# LoRa_PWR_Monitor.net
KiCad netlist of a schematic drawn in Altium Designer
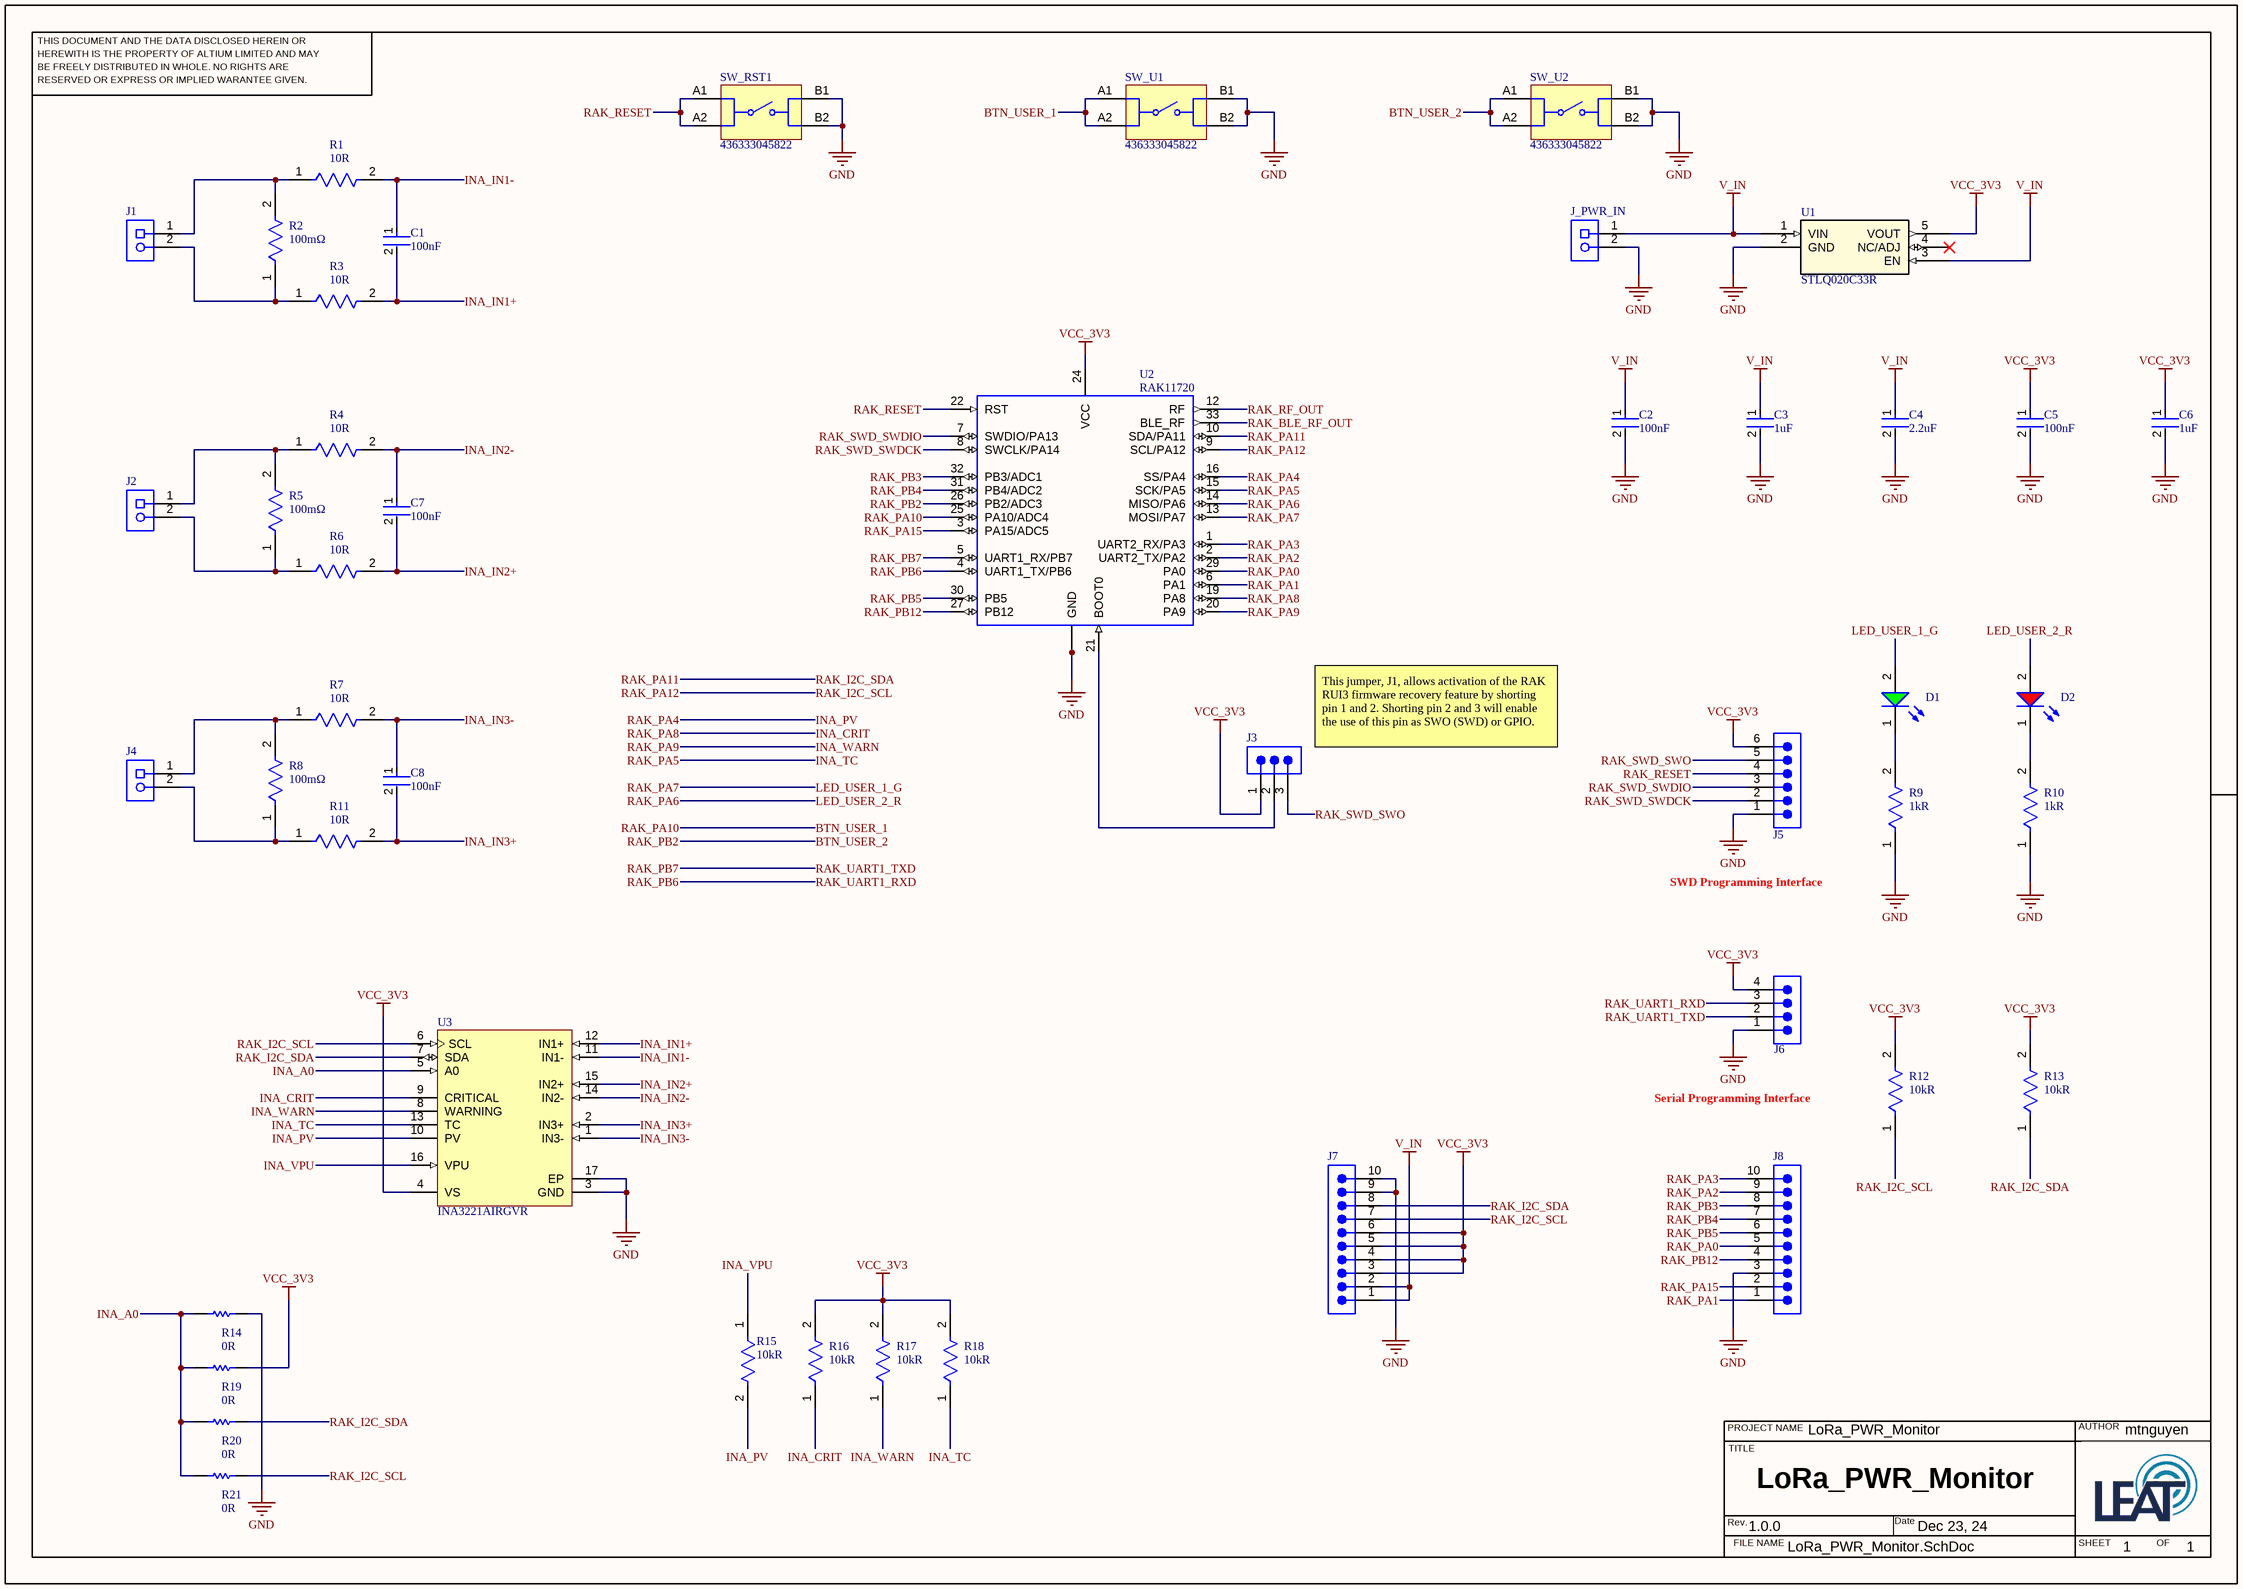
[diagram p0: LoRa_PWR_Monitor.SchDoc]

(export (version "E")
  (design (tool "Eeschema 10.0.6"))
  (components
    (comp (ref "C1")
      (value "0402ZD104KAT2A")
      (footprint "FP-0402-L_1_0_1-W_0_5_0_1-IPC_C")
      (description "General Purpose Ceramic Capacitor, 0402, 100nF, 10%, X5R, 15%, 10V")
      (fields
        (field (name "VOLTAGE") "10V")
        (field (name "TOLERANCE") "10%")
        (field (name "CAPACITANCE") "100nF")
      )
      (libsource (lib "Altium Content Vault") (part "b4654b650e69147ec39a6b967a45e02"))
    )
    (comp (ref "C2")
      (value "0402ZD104KAT2A")
      (footprint "FP-0402-L_1_0_1-W_0_5_0_1-IPC_C")
      (description "General Purpose Ceramic Capacitor, 0402, 100nF, 10%, X5R, 15%, 10V")
      (fields
        (field (name "VOLTAGE") "10V")
        (field (name "TOLERANCE") "10%")
        (field (name "CAPACITANCE") "100nF")
      )
      (libsource (lib "Altium Content Vault") (part "b4654b650e69147ec39a6b967a45e02"))
    )
    (comp (ref "C3")
      (value "EMK105BJ105KV-F")
      (footprint "FP-0402-L_1_0_0_05-W_0_5-IPC_A")
      (description "None")
      (fields (field (name "TOLERANCE") "10%") (field (name "CAPACITANCE") "1uF"))
      (libsource (lib "Altium Content Vault") (part "b4654b650e69147ec39a6b967a45e02"))
    )
    (comp (ref "C4")
      (value "C1005X5R1A225K050BC")
      (footprint "FP-C1005-050-0_05-IPC_A")
      (description "Multilayer Ceramic Capacitors 2.2μF ±10% 10V X5R SMD 0402")
      (fields
        (field (name "TOLERANCE") "10%")
        (field (name "VOLTAGE") "10V")
        (field (name "CAPACITANCE") "2.2uF")
      )
      (libsource (lib "Altium Content Vault") (part "b4654b650e69147ec39a6b967a45e02"))
    )
    (comp (ref "C5")
      (value "0402ZD104KAT2A")
      (footprint "FP-0402-L_1_0_1-W_0_5_0_1-IPC_C")
      (description "General Purpose Ceramic Capacitor, 0402, 100nF, 10%, X5R, 15%, 10V")
      (fields
        (field (name "VOLTAGE") "10V")
        (field (name "TOLERANCE") "10%")
        (field (name "CAPACITANCE") "100nF")
      )
      (libsource (lib "Altium Content Vault") (part "b4654b650e69147ec39a6b967a45e02"))
    )
    (comp (ref "C6")
      (value "EMK105BJ105KV-F")
      (footprint "FP-0402-L_1_0_0_05-W_0_5-IPC_A")
      (description "None")
      (fields (field (name "TOLERANCE") "10%") (field (name "CAPACITANCE") "1uF"))
      (libsource (lib "Altium Content Vault") (part "b4654b650e69147ec39a6b967a45e02"))
    )
    (comp (ref "C7")
      (value "0402ZD104KAT2A")
      (footprint "FP-0402-L_1_0_1-W_0_5_0_1-IPC_C")
      (description "General Purpose Ceramic Capacitor, 0402, 100nF, 10%, X5R, 15%, 10V")
      (fields
        (field (name "VOLTAGE") "10V")
        (field (name "TOLERANCE") "10%")
        (field (name "CAPACITANCE") "100nF")
      )
      (libsource (lib "Altium Content Vault") (part "b4654b650e69147ec39a6b967a45e02"))
    )
    (comp (ref "C8")
      (value "0402ZD104KAT2A")
      (footprint "FP-0402-L_1_0_1-W_0_5_0_1-IPC_C")
      (description "General Purpose Ceramic Capacitor, 0402, 100nF, 10%, X5R, 15%, 10V")
      (fields
        (field (name "VOLTAGE") "10V")
        (field (name "TOLERANCE") "10%")
        (field (name "CAPACITANCE") "100nF")
      )
      (libsource (lib "Altium Content Vault") (part "b4654b650e69147ec39a6b967a45e02"))
    )
    (comp (ref "D1")
      (value "150060VS75000")
      (footprint "WL-SMCW_0603_150060xx75000")
      (description "WURTH ELEKTRONIK - 150060VS75000 - LED, Green, SMD, 0603, 30 mA, 2 V, 570 nm")
      (libsource (lib "Altium Content Vault") (part "LED_Green_2A-1K"))
    )
    (comp (ref "D2")
      (value "150060RS75000")
      (footprint "WL-SMCW_0603_150060xx75000")
      (description "LED Low-Power Uni-Color Red 630nm 2V 2-Pin Chip 0603(1608Metric) T/R")
      (libsource (lib "Altium Content Vault") (part "LED_Red_2A-1K"))
    )
    (comp (ref "J1")
      (value "1729128")
      (footprint "PHOE-1729128-2_V")
      (description "PCB Terminal Block, 13.5 A, 400 V, 2-Pin THD, RoHS, Bulk")
      (fields (field (name "MANUFACTURER") "Phoenix Contact"))
      (libsource (lib "Altium Content Vault") (part "CN-2P-F-R2"))
    )
    (comp (ref "J2")
      (value "1729128")
      (footprint "PHOE-1729128-2_V")
      (description "PCB Terminal Block, 13.5 A, 400 V, 2-Pin THD, RoHS, Bulk")
      (fields (field (name "MANUFACTURER") "Phoenix Contact"))
      (libsource (lib "Altium Content Vault") (part "CN-2P-F-R2"))
    )
    (comp (ref "J3")
      (value "61300311121")
      (footprint "61300311121")
      (libsource (lib "Altium Content Vault") (part "Header_Male_1R_03P"))
    )
    (comp (ref "J4")
      (value "1729128")
      (footprint "PHOE-1729128-2_V")
      (description "PCB Terminal Block, 13.5 A, 400 V, 2-Pin THD, RoHS, Bulk")
      (fields (field (name "MANUFACTURER") "Phoenix Contact"))
      (libsource (lib "Altium Content Vault") (part "CN-2P-F-R2"))
    )
    (comp (ref "J5")
      (value "61300611121")
      (footprint "61300611121")
      (libsource (lib "Altium Content Vault") (part "Header_Male_1R_06P"))
    )
    (comp (ref "J6")
      (value "61300411121")
      (footprint "61300411121")
      (libsource (lib "Altium Content Vault") (part "Header_Male_1R_04P"))
    )
    (comp (ref "J7")
      (value "61301011121")
      (footprint "61301011121")
      (libsource (lib "Altium Content Vault") (part "Header_Male_1R_10P"))
    )
    (comp (ref "J8")
      (value "61301011121")
      (footprint "61301011121")
      (libsource (lib "Altium Content Vault") (part "Header_Male_1R_10P"))
    )
    (comp (ref "J_PWR_IN")
      (value "1729128")
      (footprint "PHOE-1729128-2_V")
      (description "PCB Terminal Block, 13.5 A, 400 V, 2-Pin THD, RoHS, Bulk")
      (fields (field (name "MANUFACTURER") "Phoenix Contact"))
      (libsource (lib "Altium Content Vault") (part "CN-2P-F-R2"))
    )
    (comp (ref "R1")
      (value "MCR01MZPF10R0")
      (footprint "FP-MCR01-IPC_C")
      (description "Thick Film Chip Resistor, 0402, 10Ω, 1%, 100ppm/°C, 0.063W, 50V")
      (fields (field (name "RESISTANCE") "10R") (field (name "TOLERANCE") "1%"))
      (libsource (lib "Altium Content Vault") (part "1029c3af85768c4190bb7ad29bc67b5"))
    )
    (comp (ref "R2")
      (value "100mΩ")
      (footprint "FP-CRM2512-MFG")
      (description "RES 0.1 OHM 1% 2W 2512")
      (fields (field (name "MANUFACTURER") "Bourns") (field (name "VOLTAGE") "1.349V"))
      (libsource (lib "Altium Content Vault") (part "1029c3af85768c4190bb7ad29bc67b5"))
    )
    (comp (ref "R3")
      (value "MCR01MZPF10R0")
      (footprint "FP-MCR01-IPC_C")
      (description "Thick Film Chip Resistor, 0402, 10Ω, 1%, 100ppm/°C, 0.063W, 50V")
      (fields (field (name "RESISTANCE") "10R") (field (name "TOLERANCE") "1%"))
      (libsource (lib "Altium Content Vault") (part "1029c3af85768c4190bb7ad29bc67b5"))
    )
    (comp (ref "R4")
      (value "MCR01MZPF10R0")
      (footprint "FP-MCR01-IPC_C")
      (description "Thick Film Chip Resistor, 0402, 10Ω, 1%, 100ppm/°C, 0.063W, 50V")
      (fields (field (name "RESISTANCE") "10R") (field (name "TOLERANCE") "1%"))
      (libsource (lib "Altium Content Vault") (part "1029c3af85768c4190bb7ad29bc67b5"))
    )
    (comp (ref "R5")
      (value "100mΩ")
      (footprint "FP-CRM2512-MFG")
      (description "RES 0.1 OHM 1% 2W 2512")
      (fields (field (name "MANUFACTURER") "Bourns") (field (name "VOLTAGE") "1.349V"))
      (libsource (lib "Altium Content Vault") (part "1029c3af85768c4190bb7ad29bc67b5"))
    )
    (comp (ref "R6")
      (value "MCR01MZPF10R0")
      (footprint "FP-MCR01-IPC_C")
      (description "Thick Film Chip Resistor, 0402, 10Ω, 1%, 100ppm/°C, 0.063W, 50V")
      (fields (field (name "RESISTANCE") "10R") (field (name "TOLERANCE") "1%"))
      (libsource (lib "Altium Content Vault") (part "1029c3af85768c4190bb7ad29bc67b5"))
    )
    (comp (ref "R7")
      (value "MCR01MZPF10R0")
      (footprint "FP-MCR01-IPC_C")
      (description "Thick Film Chip Resistor, 0402, 10Ω, 1%, 100ppm/°C, 0.063W, 50V")
      (fields (field (name "RESISTANCE") "10R") (field (name "TOLERANCE") "1%"))
      (libsource (lib "Altium Content Vault") (part "1029c3af85768c4190bb7ad29bc67b5"))
    )
    (comp (ref "R8")
      (value "100mΩ")
      (footprint "FP-CRM2512-MFG")
      (description "RES 0.1 OHM 1% 2W 2512")
      (fields (field (name "MANUFACTURER") "Bourns") (field (name "VOLTAGE") "1.349V"))
      (libsource (lib "Altium Content Vault") (part "1029c3af85768c4190bb7ad29bc67b5"))
    )
    (comp (ref "R9")
      (value "RMCF0402FT1K00")
      (footprint "FP-RMCF0402-IPC_A")
      (description "1kΩ ±1% 0.063W 0402 Thick Film Chip Resistor AEC-Q200 compliant")
      (fields (field (name "TOLERANCE") "1%") (field (name "RESISTANCE") "1kR"))
      (libsource (lib "Altium Content Vault") (part "1029c3af85768c4190bb7ad29bc67b5"))
    )
    (comp (ref "R10")
      (value "RMCF0402FT1K00")
      (footprint "FP-RMCF0402-IPC_A")
      (description "1kΩ ±1% 0.063W 0402 Thick Film Chip Resistor AEC-Q200 compliant")
      (fields (field (name "TOLERANCE") "1%") (field (name "RESISTANCE") "1kR"))
      (libsource (lib "Altium Content Vault") (part "1029c3af85768c4190bb7ad29bc67b5"))
    )
    (comp (ref "R11")
      (value "MCR01MZPF10R0")
      (footprint "FP-MCR01-IPC_C")
      (description "Thick Film Chip Resistor, 0402, 10Ω, 1%, 100ppm/°C, 0.063W, 50V")
      (fields (field (name "RESISTANCE") "10R") (field (name "TOLERANCE") "1%"))
      (libsource (lib "Altium Content Vault") (part "1029c3af85768c4190bb7ad29bc67b5"))
    )
    (comp (ref "R12")
      (value "RMCF0402FT10K0")
      (footprint "FP-RMCF0402-IPC_C")
      (description "10kΩ ±1% 0.063W 0402 Thick Film Chip Resistor AEC-Q200 compliant")
      (fields (field (name "RESISTANCE") "10kR") (field (name "TOLERANCE") "1%"))
      (libsource (lib "Altium Content Vault") (part "1029c3af85768c4190bb7ad29bc67b5"))
    )
    (comp (ref "R13")
      (value "RMCF0402FT10K0")
      (footprint "FP-RMCF0402-IPC_C")
      (description "10kΩ ±1% 0.063W 0402 Thick Film Chip Resistor AEC-Q200 compliant")
      (fields (field (name "RESISTANCE") "10kR") (field (name "TOLERANCE") "1%"))
      (libsource (lib "Altium Content Vault") (part "1029c3af85768c4190bb7ad29bc67b5"))
    )
    (comp (ref "R14")
      (value "RC1005J000CS")
      (footprint "RESC1005X40X25LL05T10")
      (description "Chip Resistor, 0 Ohm, +/- 5%, -55 to 125 degC, 0402 (1005 Metric), RoHS, Tape and Reel")
      (fields (field (name "RESISTANCE") "0R") (field (name "MANUFACTURER") "Samsung Electro-Mechanics"))
      (libsource (lib "Altium Content Vault") (part "RES-2"))
    )
    (comp (ref "R15")
      (value "RMCF0402FT10K0")
      (footprint "FP-RMCF0402-IPC_C")
      (description "10kΩ ±1% 0.063W 0402 Thick Film Chip Resistor AEC-Q200 compliant")
      (fields (field (name "RESISTANCE") "10kR") (field (name "TOLERANCE") "1%"))
      (libsource (lib "Altium Content Vault") (part "1029c3af85768c4190bb7ad29bc67b5"))
    )
    (comp (ref "R16")
      (value "RMCF0402FT10K0")
      (footprint "FP-RMCF0402-IPC_C")
      (description "10kΩ ±1% 0.063W 0402 Thick Film Chip Resistor AEC-Q200 compliant")
      (fields (field (name "RESISTANCE") "10kR") (field (name "TOLERANCE") "1%"))
      (libsource (lib "Altium Content Vault") (part "1029c3af85768c4190bb7ad29bc67b5"))
    )
    (comp (ref "R17")
      (value "RMCF0402FT10K0")
      (footprint "FP-RMCF0402-IPC_C")
      (description "10kΩ ±1% 0.063W 0402 Thick Film Chip Resistor AEC-Q200 compliant")
      (fields (field (name "RESISTANCE") "10kR") (field (name "TOLERANCE") "1%"))
      (libsource (lib "Altium Content Vault") (part "1029c3af85768c4190bb7ad29bc67b5"))
    )
    (comp (ref "R18")
      (value "RMCF0402FT10K0")
      (footprint "FP-RMCF0402-IPC_C")
      (description "10kΩ ±1% 0.063W 0402 Thick Film Chip Resistor AEC-Q200 compliant")
      (fields (field (name "RESISTANCE") "10kR") (field (name "TOLERANCE") "1%"))
      (libsource (lib "Altium Content Vault") (part "1029c3af85768c4190bb7ad29bc67b5"))
    )
    (comp (ref "R19")
      (value "RC1005J000CS")
      (footprint "RESC1005X40X25LL05T10")
      (description "Chip Resistor, 0 Ohm, +/- 5%, -55 to 125 degC, 0402 (1005 Metric), RoHS, Tape and Reel")
      (fields (field (name "RESISTANCE") "0R") (field (name "MANUFACTURER") "Samsung Electro-Mechanics"))
      (libsource (lib "Altium Content Vault") (part "RES-2"))
    )
    (comp (ref "R20")
      (value "RC1005J000CS")
      (footprint "RESC1005X40X25LL05T10")
      (description "Chip Resistor, 0 Ohm, +/- 5%, -55 to 125 degC, 0402 (1005 Metric), RoHS, Tape and Reel")
      (fields (field (name "RESISTANCE") "0R") (field (name "MANUFACTURER") "Samsung Electro-Mechanics"))
      (libsource (lib "Altium Content Vault") (part "RES-2"))
    )
    (comp (ref "R21")
      (value "RC1005J000CS")
      (footprint "RESC1005X40X25LL05T10")
      (description "Chip Resistor, 0 Ohm, +/- 5%, -55 to 125 degC, 0402 (1005 Metric), RoHS, Tape and Reel")
      (fields (field (name "RESISTANCE") "0R") (field (name "MANUFACTURER") "Samsung Electro-Mechanics"))
      (libsource (lib "Altium Content Vault") (part "RES-2"))
    )
    (comp (ref "SW_RST1")
      (value "436333045822")
      (footprint "436333045822")
      (libsource (lib "Altium Content Vault") (part "SPST-NO_4P"))
    )
    (comp (ref "SW_U1")
      (value "436333045822")
      (footprint "436333045822")
      (libsource (lib "Altium Content Vault") (part "SPST-NO_4P"))
    )
    (comp (ref "SW_U2")
      (value "436333045822")
      (footprint "436333045822")
      (libsource (lib "Altium Content Vault") (part "SPST-NO_4P"))
    )
    (comp (ref "U1")
      (value "STLQ020C33R")
      (footprint "SOT323-5L_STM")
      (description "No Description Available")
      (fields (field (name "COPYRIGHT") "Copyright (C) 2023 Ultra Librarian. All rights reserved."))
      (libsource (lib "EchoStar") (part "STLQ020C33R"))
    )
    (comp (ref "U2")
      (value "RAK11720")
      (footprint "RAK11720")
      (description "RAK11720 Ambiq Apollo3 Blue SX1262 LoRa Bluetooth Module for LoRaWAN")
      (fields (field (name "MP") "RAK3172") (field (name "MF") "Shenzhen RAKwireless Technology Co.,Ltd."))
      (libsource (lib "RAK3172") (part "RAK11720"))
    )
    (comp (ref "U3")
      (value "INA3221AIRGVR")
      (footprint "RGV0016A_V")
      (fields (field (name "MANUFACTURER") "Texas Instruments"))
      (libsource (lib "Altium Content Vault") (part "TI-INA3221-RGV-16"))
    )
  )
  (nets
    (net (code "1") (name "/BTN_USER_1") (class "Default")
      (node (ref "SW_U1") (pin "A1") (pinfunction "A1_A1") (pintype "passive"))
      (node (ref "SW_U1") (pin "A2") (pinfunction "A2_A2") (pintype "passive"))
      (node (ref "U2") (pin "25") (pinfunction "PA10/ADC4_25") (pintype "bidirectional"))
    )
    (net (code "2") (name "/BTN_USER_2") (class "Default")
      (node (ref "SW_U2") (pin "A1") (pinfunction "A1_A1") (pintype "passive"))
      (node (ref "SW_U2") (pin "A2") (pinfunction "A2_A2") (pintype "passive"))
      (node (ref "U2") (pin "26") (pinfunction "PB2/ADC3_26") (pintype "bidirectional"))
    )
    (net (code "3") (name "/INA_A0") (class "Default")
      (node (ref "R14") (pin "1") (pinfunction "1_1") (pintype "passive"))
      (node (ref "R19") (pin "1") (pinfunction "1_1") (pintype "passive"))
      (node (ref "R20") (pin "1") (pinfunction "1_1") (pintype "passive"))
      (node (ref "R21") (pin "1") (pinfunction "1_1") (pintype "passive"))
      (node (ref "U3") (pin "5") (pinfunction "A0_5") (pintype "input"))
    )
    (net (code "4") (name "/INA_CRIT") (class "Default")
      (node (ref "R16") (pin "1") (pinfunction "1_1") (pintype "passive"))
      (node (ref "U2") (pin "19") (pinfunction "PA8_19") (pintype "bidirectional"))
      (node (ref "U3") (pin "9") (pinfunction "CRITICAL_9") (pintype "open_collector"))
    )
    (net (code "5") (name "/INA_IN1+") (class "Default")
      (node (ref "C1") (pin "2") (pinfunction "2_2") (pintype "passive"))
      (node (ref "R3") (pin "2") (pinfunction "2_2") (pintype "passive"))
      (node (ref "U3") (pin "12") (pinfunction "IN1+_12") (pintype "input"))
    )
    (net (code "6") (name "/INA_IN1-") (class "Default")
      (node (ref "C1") (pin "1") (pinfunction "1_1") (pintype "passive"))
      (node (ref "R1") (pin "2") (pinfunction "2_2") (pintype "passive"))
      (node (ref "U3") (pin "11") (pinfunction "IN1-_11") (pintype "input"))
    )
    (net (code "7") (name "/INA_IN2+") (class "Default")
      (node (ref "C7") (pin "2") (pinfunction "2_2") (pintype "passive"))
      (node (ref "R6") (pin "2") (pinfunction "2_2") (pintype "passive"))
      (node (ref "U3") (pin "15") (pinfunction "IN2+_15") (pintype "input"))
    )
    (net (code "8") (name "/INA_IN2-") (class "Default")
      (node (ref "C7") (pin "1") (pinfunction "1_1") (pintype "passive"))
      (node (ref "R4") (pin "2") (pinfunction "2_2") (pintype "passive"))
      (node (ref "U3") (pin "14") (pinfunction "IN2-_14") (pintype "input"))
    )
    (net (code "9") (name "/INA_IN3+") (class "Default")
      (node (ref "C8") (pin "2") (pinfunction "2_2") (pintype "passive"))
      (node (ref "R11") (pin "2") (pinfunction "2_2") (pintype "passive"))
      (node (ref "U3") (pin "2") (pinfunction "IN3+_2") (pintype "input"))
    )
    (net (code "10") (name "/INA_IN3-") (class "Default")
      (node (ref "C8") (pin "1") (pinfunction "1_1") (pintype "passive"))
      (node (ref "R7") (pin "2") (pinfunction "2_2") (pintype "passive"))
      (node (ref "U3") (pin "1") (pinfunction "IN3-_1") (pintype "input"))
    )
    (net (code "11") (name "/INA_PV") (class "Default")
      (node (ref "R15") (pin "2") (pinfunction "2_2") (pintype "passive"))
      (node (ref "U2") (pin "16") (pinfunction "SS/PA4_16") (pintype "bidirectional"))
      (node (ref "U3") (pin "10") (pinfunction "PV_10") (pintype "open_collector"))
    )
    (net (code "12") (name "/INA_TC") (class "Default")
      (node (ref "R18") (pin "1") (pinfunction "1_1") (pintype "passive"))
      (node (ref "U2") (pin "15") (pinfunction "SCK/PA5_15") (pintype "bidirectional"))
      (node (ref "U3") (pin "13") (pinfunction "TC_13") (pintype "open_collector"))
    )
    (net (code "13") (name "/INA_VPU") (class "Default")
      (node (ref "R15") (pin "1") (pinfunction "1_1") (pintype "passive"))
      (node (ref "U3") (pin "16") (pinfunction "VPU_16") (pintype "input"))
    )
    (net (code "14") (name "/INA_WARN") (class "Default")
      (node (ref "R17") (pin "1") (pinfunction "1_1") (pintype "passive"))
      (node (ref "U2") (pin "20") (pinfunction "PA9_20") (pintype "bidirectional"))
      (node (ref "U3") (pin "8") (pinfunction "WARNING_8") (pintype "open_collector"))
    )
    (net (code "15") (name "/LED_USER_1_G") (class "Default")
      (node (ref "D1") (pin "2") (pinfunction "A_2") (pintype "passive"))
      (node (ref "U2") (pin "13") (pinfunction "MOSI/PA7_13") (pintype "bidirectional"))
    )
    (net (code "16") (name "/LED_USER_2_R") (class "Default")
      (node (ref "D2") (pin "2") (pinfunction "A_2") (pintype "passive"))
      (node (ref "U2") (pin "14") (pinfunction "MISO/PA6_14") (pintype "bidirectional"))
    )
    (net (code "17") (name "/RAK_BLE_RF_OUT") (class "Default")
      (node (ref "U2") (pin "33") (pinfunction "BLE_RF_33") (pintype "output"))
    )
    (net (code "18") (name "/RAK_I2C_SCL") (class "Default")
      (node (ref "J7") (pin "7") (pinfunction "7_7") (pintype "passive"))
      (node (ref "R12") (pin "1") (pinfunction "1_1") (pintype "passive"))
      (node (ref "R21") (pin "2") (pinfunction "2_2") (pintype "passive"))
      (node (ref "U2") (pin "9") (pinfunction "SCL/PA12_9") (pintype "bidirectional"))
      (node (ref "U3") (pin "6") (pinfunction "SCL_6") (pintype "input"))
    )
    (net (code "19") (name "/RAK_I2C_SDA") (class "Default")
      (node (ref "J7") (pin "8") (pinfunction "8_8") (pintype "passive"))
      (node (ref "R13") (pin "1") (pinfunction "1_1") (pintype "passive"))
      (node (ref "R20") (pin "2") (pinfunction "2_2") (pintype "passive"))
      (node (ref "U2") (pin "10") (pinfunction "SDA/PA11_10") (pintype "bidirectional"))
      (node (ref "U3") (pin "7") (pinfunction "SDA_7") (pintype "bidirectional"))
    )
    (net (code "20") (name "/RAK_PA0") (class "Default")
      (node (ref "J8") (pin "5") (pinfunction "5_5") (pintype "passive"))
      (node (ref "U2") (pin "29") (pinfunction "PA0_29") (pintype "bidirectional"))
    )
    (net (code "21") (name "/RAK_PA1") (class "Default")
      (node (ref "J8") (pin "1") (pinfunction "1_1") (pintype "passive"))
      (node (ref "U2") (pin "6") (pinfunction "PA1_6") (pintype "bidirectional"))
    )
    (net (code "22") (name "/RAK_PA2") (class "Default")
      (node (ref "J8") (pin "9") (pinfunction "9_9") (pintype "passive"))
      (node (ref "U2") (pin "2") (pinfunction "UART2_TX/PA2_2") (pintype "bidirectional"))
    )
    (net (code "23") (name "/RAK_PA3") (class "Default")
      (node (ref "J8") (pin "10") (pinfunction "10_10") (pintype "passive"))
      (node (ref "U2") (pin "1") (pinfunction "UART2_RX/PA3_1") (pintype "bidirectional"))
    )
    (net (code "24") (name "/RAK_PA15") (class "Default")
      (node (ref "J8") (pin "2") (pinfunction "2_2") (pintype "passive"))
      (node (ref "U2") (pin "3") (pinfunction "PA15/ADC5_3") (pintype "bidirectional"))
    )
    (net (code "25") (name "/RAK_PB3") (class "Default")
      (node (ref "J8") (pin "8") (pinfunction "8_8") (pintype "passive"))
      (node (ref "U2") (pin "32") (pinfunction "PB3/ADC1_32") (pintype "bidirectional"))
    )
    (net (code "26") (name "/RAK_PB4") (class "Default")
      (node (ref "J8") (pin "7") (pinfunction "7_7") (pintype "passive"))
      (node (ref "U2") (pin "31") (pinfunction "PB4/ADC2_31") (pintype "bidirectional"))
    )
    (net (code "27") (name "/RAK_PB5") (class "Default")
      (node (ref "J8") (pin "6") (pinfunction "6_6") (pintype "passive"))
      (node (ref "U2") (pin "30") (pinfunction "PB5_30") (pintype "bidirectional"))
    )
    (net (code "28") (name "/RAK_PB6") (class "Default")
      (node (ref "J6") (pin "3") (pinfunction "3_3") (pintype "passive"))
      (node (ref "U2") (pin "4") (pinfunction "UART1_TX/PB6_4") (pintype "bidirectional"))
    )
    (net (code "29") (name "/RAK_PB7") (class "Default")
      (node (ref "J6") (pin "2") (pinfunction "2_2") (pintype "passive"))
      (node (ref "U2") (pin "5") (pinfunction "UART1_RX/PB7_5") (pintype "bidirectional"))
    )
    (net (code "30") (name "/RAK_PB12") (class "Default")
      (node (ref "J8") (pin "4") (pinfunction "4_4") (pintype "passive"))
      (node (ref "U2") (pin "27") (pinfunction "PB12_27") (pintype "bidirectional"))
    )
    (net (code "31") (name "/RAK_RESET") (class "Default")
      (node (ref "J5") (pin "4") (pinfunction "4_4") (pintype "passive"))
      (node (ref "SW_RST1") (pin "A1") (pinfunction "A1_A1") (pintype "passive"))
      (node (ref "SW_RST1") (pin "A2") (pinfunction "A2_A2") (pintype "passive"))
      (node (ref "U2") (pin "22") (pinfunction "RST_22") (pintype "input"))
    )
    (net (code "32") (name "/RAK_RF_OUT") (class "Default")
      (node (ref "U2") (pin "12") (pinfunction "RF_12") (pintype "output"))
    )
    (net (code "33") (name "/RAK_SWD_SWDCK") (class "Default")
      (node (ref "J5") (pin "2") (pinfunction "2_2") (pintype "passive"))
      (node (ref "U2") (pin "8") (pinfunction "SWCLK/PA14_8") (pintype "bidirectional"))
    )
    (net (code "34") (name "/RAK_SWD_SWDIO") (class "Default")
      (node (ref "J5") (pin "3") (pinfunction "3_3") (pintype "passive"))
      (node (ref "U2") (pin "7") (pinfunction "SWDIO/PA13_7") (pintype "bidirectional"))
    )
    (net (code "35") (name "/RAK_SWD_SWO") (class "Default")
      (node (ref "J3") (pin "3") (pinfunction "3_3") (pintype "passive"))
      (node (ref "J5") (pin "5") (pinfunction "5_5") (pintype "passive"))
    )
    (net (code "36") (name "GND") (class "Default")
      (node (ref "C2") (pin "2") (pinfunction "2_2") (pintype "passive"))
      (node (ref "C3") (pin "2") (pinfunction "2_2") (pintype "passive"))
      (node (ref "C4") (pin "2") (pinfunction "2_2") (pintype "passive"))
      (node (ref "C5") (pin "2") (pinfunction "2_2") (pintype "passive"))
      (node (ref "C6") (pin "2") (pinfunction "2_2") (pintype "passive"))
      (node (ref "J5") (pin "1") (pinfunction "1_1") (pintype "passive"))
      (node (ref "J6") (pin "1") (pinfunction "1_1") (pintype "passive"))
      (node (ref "J7") (pin "10") (pinfunction "10_10") (pintype "passive"))
      (node (ref "J7") (pin "9") (pinfunction "9_9") (pintype "passive"))
      (node (ref "J8") (pin "3") (pinfunction "3_3") (pintype "passive"))
      (node (ref "J_PWR_IN") (pin "2") (pinfunction "2_2") (pintype "passive"))
      (node (ref "R10") (pin "1") (pinfunction "1_1") (pintype "passive"))
      (node (ref "R14") (pin "2") (pinfunction "2_2") (pintype "passive"))
      (node (ref "R9") (pin "1") (pinfunction "1_1") (pintype "passive"))
      (node (ref "SW_RST1") (pin "B1") (pinfunction "B1_B1") (pintype "passive"))
      (node (ref "SW_RST1") (pin "B2") (pinfunction "B2_B2") (pintype "passive"))
      (node (ref "SW_U1") (pin "B1") (pinfunction "B1_B1") (pintype "passive"))
      (node (ref "SW_U1") (pin "B2") (pinfunction "B2_B2") (pintype "passive"))
      (node (ref "SW_U2") (pin "B1") (pinfunction "B1_B1") (pintype "passive"))
      (node (ref "SW_U2") (pin "B2") (pinfunction "B2_B2") (pintype "passive"))
      (node (ref "U1") (pin "2") (pinfunction "GND_2") (pintype "power_in"))
      (node (ref "U2") (pin "11") (pinfunction "GND_11") (pintype "power_in"))
      (node (ref "U2") (pin "17") (pinfunction "GND_17") (pintype "power_in"))
      (node (ref "U2") (pin "18") (pinfunction "GND_18") (pintype "power_in"))
      (node (ref "U2") (pin "23") (pinfunction "GND_23") (pintype "power_in"))
      (node (ref "U2") (pin "28") (pinfunction "GND_28") (pintype "power_in"))
      (node (ref "U2") (pin "34") (pinfunction "GND_34") (pintype "power_in"))
      (node (ref "U3") (pin "17") (pinfunction "EP_17") (pintype "passive"))
      (node (ref "U3") (pin "3") (pinfunction "GND_3") (pintype "power_in"))
    )
    (net (code "37") (name "Net-(D1-K)") (class "Default")
      (node (ref "D1") (pin "1") (pinfunction "K_1") (pintype "passive"))
      (node (ref "R9") (pin "2") (pinfunction "2_2") (pintype "passive"))
    )
    (net (code "38") (name "Net-(D2-K)") (class "Default")
      (node (ref "D2") (pin "1") (pinfunction "K_1") (pintype "passive"))
      (node (ref "R10") (pin "2") (pinfunction "2_2") (pintype "passive"))
    )
    (net (code "39") (name "Net-(J1-Pad1)") (class "Default")
      (node (ref "J1") (pin "1") (pinfunction "1_1") (pintype "passive"))
      (node (ref "R1") (pin "1") (pinfunction "1_1") (pintype "passive"))
      (node (ref "R2") (pin "2") (pinfunction "2_2") (pintype "passive"))
    )
    (net (code "40") (name "Net-(J1-Pad2)") (class "Default")
      (node (ref "J1") (pin "2") (pinfunction "2_2") (pintype "passive"))
      (node (ref "R2") (pin "1") (pinfunction "1_1") (pintype "passive"))
      (node (ref "R3") (pin "1") (pinfunction "1_1") (pintype "passive"))
    )
    (net (code "41") (name "Net-(J2-Pad1)") (class "Default")
      (node (ref "J2") (pin "1") (pinfunction "1_1") (pintype "passive"))
      (node (ref "R4") (pin "1") (pinfunction "1_1") (pintype "passive"))
      (node (ref "R5") (pin "2") (pinfunction "2_2") (pintype "passive"))
    )
    (net (code "42") (name "Net-(J2-Pad2)") (class "Default")
      (node (ref "J2") (pin "2") (pinfunction "2_2") (pintype "passive"))
      (node (ref "R5") (pin "1") (pinfunction "1_1") (pintype "passive"))
      (node (ref "R6") (pin "1") (pinfunction "1_1") (pintype "passive"))
    )
    (net (code "43") (name "Net-(J4-Pad1)") (class "Default")
      (node (ref "J4") (pin "1") (pinfunction "1_1") (pintype "passive"))
      (node (ref "R7") (pin "1") (pinfunction "1_1") (pintype "passive"))
      (node (ref "R8") (pin "2") (pinfunction "2_2") (pintype "passive"))
    )
    (net (code "44") (name "Net-(J4-Pad2)") (class "Default")
      (node (ref "J4") (pin "2") (pinfunction "2_2") (pintype "passive"))
      (node (ref "R11") (pin "1") (pinfunction "1_1") (pintype "passive"))
      (node (ref "R8") (pin "1") (pinfunction "1_1") (pintype "passive"))
    )
    (net (code "45") (name "Net-(U2-BOOT0)") (class "Default")
      (node (ref "J3") (pin "2") (pinfunction "2_2") (pintype "passive"))
      (node (ref "U2") (pin "21") (pinfunction "BOOT0_21") (pintype "input"))
    )
    (net (code "46") (name "VCC_3V3") (class "Default")
      (node (ref "C5") (pin "1") (pinfunction "1_1") (pintype "passive"))
      (node (ref "C6") (pin "1") (pinfunction "1_1") (pintype "passive"))
      (node (ref "J3") (pin "1") (pinfunction "1_1") (pintype "passive"))
      (node (ref "J5") (pin "6") (pinfunction "6_6") (pintype "passive"))
      (node (ref "J6") (pin "4") (pinfunction "4_4") (pintype "passive"))
      (node (ref "J7") (pin "3") (pinfunction "3_3") (pintype "passive"))
      (node (ref "J7") (pin "4") (pinfunction "4_4") (pintype "passive"))
      (node (ref "J7") (pin "5") (pinfunction "5_5") (pintype "passive"))
      (node (ref "J7") (pin "6") (pinfunction "6_6") (pintype "passive"))
      (node (ref "R12") (pin "2") (pinfunction "2_2") (pintype "passive"))
      (node (ref "R13") (pin "2") (pinfunction "2_2") (pintype "passive"))
      (node (ref "R16") (pin "2") (pinfunction "2_2") (pintype "passive"))
      (node (ref "R17") (pin "2") (pinfunction "2_2") (pintype "passive"))
      (node (ref "R18") (pin "2") (pinfunction "2_2") (pintype "passive"))
      (node (ref "R19") (pin "2") (pinfunction "2_2") (pintype "passive"))
      (node (ref "U1") (pin "5") (pinfunction "VOUT_5") (pintype "output"))
      (node (ref "U2") (pin "24") (pinfunction "VCC_24") (pintype "power_in"))
      (node (ref "U3") (pin "4") (pinfunction "VS_4") (pintype "power_in"))
    )
    (net (code "47") (name "V_IN") (class "Default")
      (node (ref "C2") (pin "1") (pinfunction "1_1") (pintype "passive"))
      (node (ref "C3") (pin "1") (pinfunction "1_1") (pintype "passive"))
      (node (ref "C4") (pin "1") (pinfunction "1_1") (pintype "passive"))
      (node (ref "J7") (pin "1") (pinfunction "1_1") (pintype "passive"))
      (node (ref "J7") (pin "2") (pinfunction "2_2") (pintype "passive"))
      (node (ref "J_PWR_IN") (pin "1") (pinfunction "1_1") (pintype "passive"))
      (node (ref "U1") (pin "1") (pinfunction "VIN_1") (pintype "input"))
      (node (ref "U1") (pin "3") (pinfunction "EN_3") (pintype "input"))
    )
    (net (code "48") (name "unconnected-(U1-NC{slash}ADJ-Pad4)") (class "Default")
      (node (ref "U1") (pin "4") (pinfunction "NC/ADJ_4") (pintype "bidirectional+no_connect"))
    )
  )
)
